# plugstrip.net
KiCad netlist of a schematic drawn in EAGLE
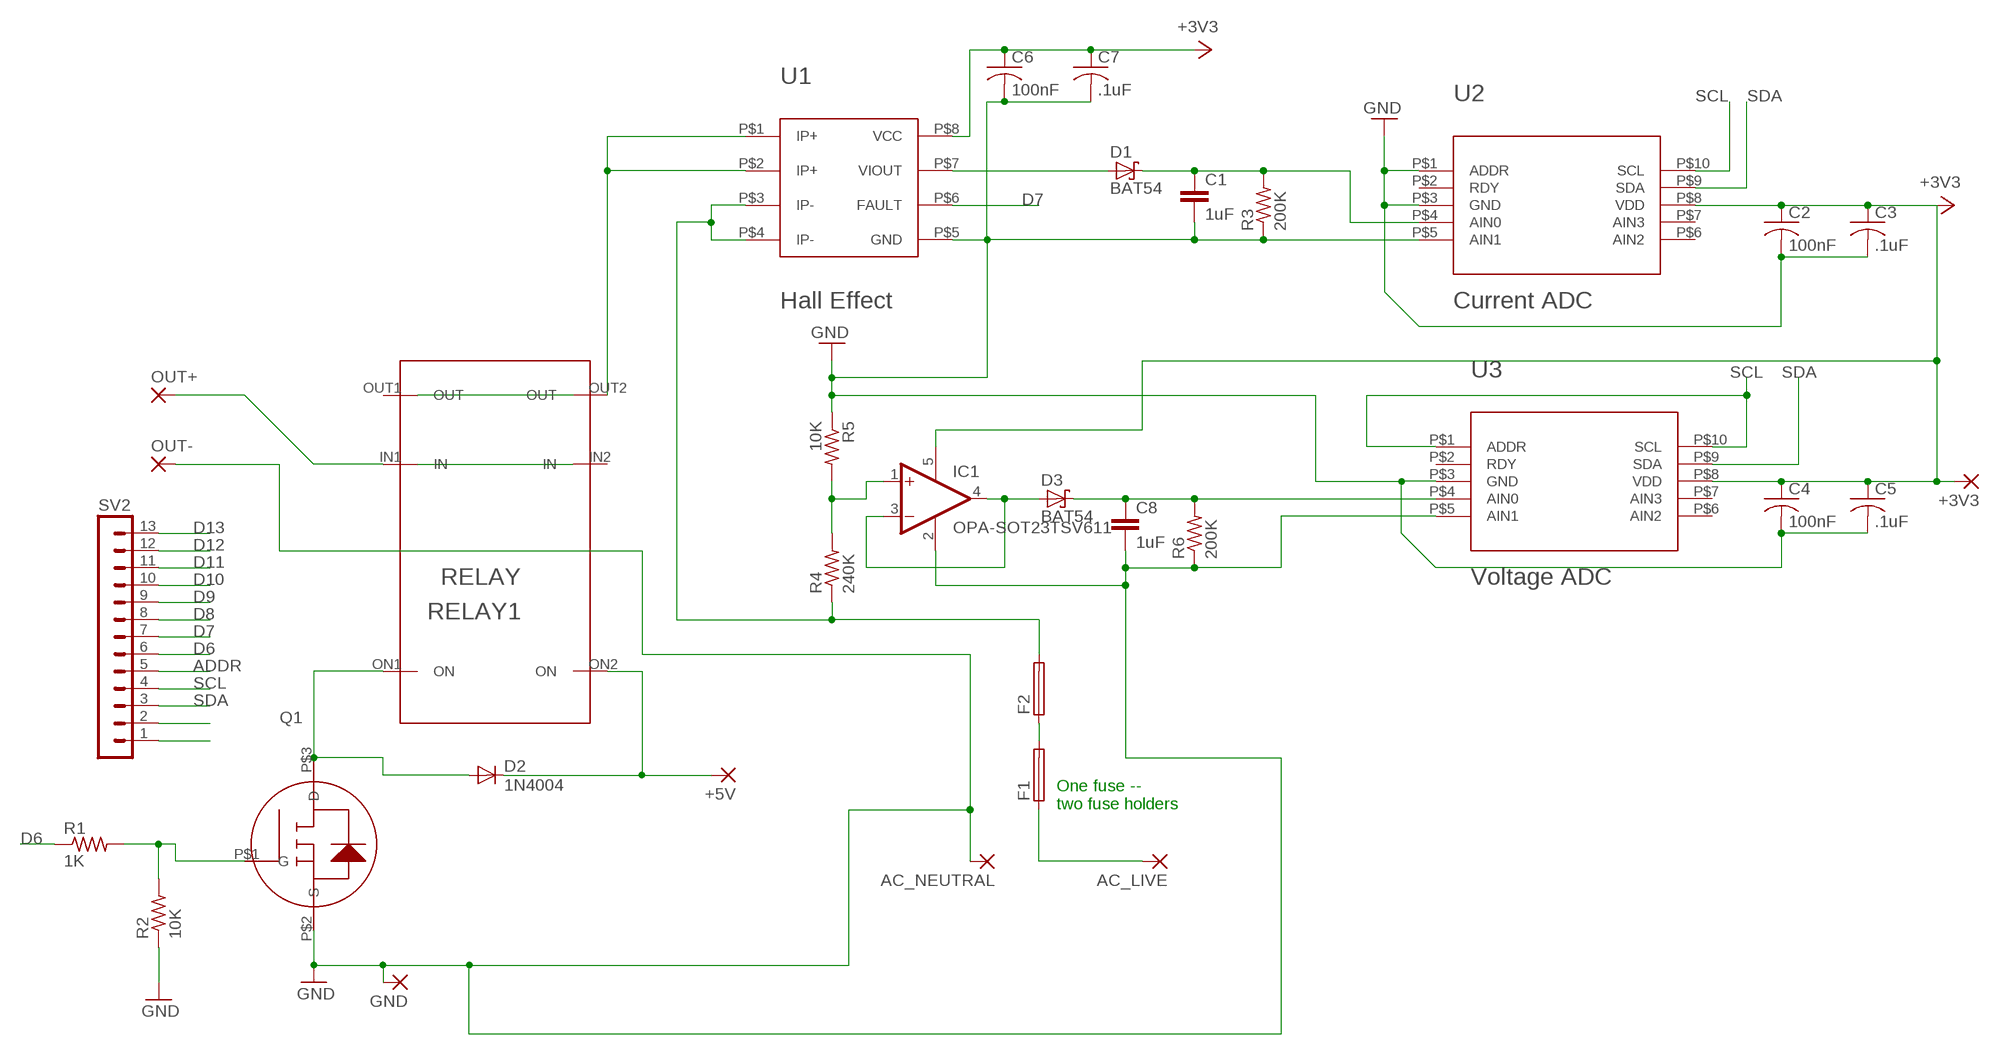
[diagram p0: schematic, sheet 1]

(export (version "E")
  (design (tool "Eeschema 10.0.6"))
  (components
    (comp (ref "+3V3")
      (value "3,81/1,4")
      (footprint "eagle-import:3,81_1,4")
      (libsource (lib "eagle-import") (part "3,81/1,4"))
    )
    (comp (ref "+5V")
      (value "3,81/1,4")
      (footprint "eagle-import:3,81_1,4")
      (libsource (lib "eagle-import") (part "3,81/1,4"))
    )
    (comp (ref "AC_LIVE")
      (value "3,81/1,4")
      (footprint "eagle-import:3,81_1,4")
      (libsource (lib "eagle-import") (part "3,81/1,4"))
    )
    (comp (ref "AC_NEUTRAL")
      (value "3,81/1,4")
      (footprint "eagle-import:3,81_1,4")
      (libsource (lib "eagle-import") (part "3,81/1,4"))
    )
    (comp (ref "C1")
      (value "1uF")
      (footprint "eagle-import:C2.5-2")
      (libsource (lib "eagle-import") (part "CSR215E105"))
    )
    (comp (ref "C2")
      (value "100nF")
      (footprint "eagle-import:C1206")
      (libsource (lib "eagle-import") (part "C-USC1206"))
    )
    (comp (ref "C3")
      (value ".1uF")
      (footprint "eagle-import:C1206")
      (libsource (lib "eagle-import") (part "C-USC1206"))
    )
    (comp (ref "C4")
      (value "100nF")
      (footprint "eagle-import:C1206")
      (libsource (lib "eagle-import") (part "C-USC1206"))
    )
    (comp (ref "C5")
      (value ".1uF")
      (footprint "eagle-import:C1206")
      (libsource (lib "eagle-import") (part "C-USC1206"))
    )
    (comp (ref "C6")
      (value "100nF")
      (footprint "eagle-import:C1206")
      (libsource (lib "eagle-import") (part "C-USC1206"))
    )
    (comp (ref "C7")
      (value ".1uF")
      (footprint "eagle-import:C1206")
      (libsource (lib "eagle-import") (part "C-USC1206"))
    )
    (comp (ref "C8")
      (value "1uF")
      (footprint "eagle-import:C2.5-2")
      (libsource (lib "eagle-import") (part "CSR215E105"))
    )
    (comp (ref "D1")
      (value "BAT54")
      (footprint "eagle-import:SOT23")
      (libsource (lib "eagle-import") (part "BAT54"))
    )
    (comp (ref "D2")
      (value "1N4004")
      (footprint "eagle-import:DO41-10")
      (libsource (lib "eagle-import") (part "1N4004"))
    )
    (comp (ref "D3")
      (value "BAT54")
      (footprint "eagle-import:SOT23")
      (libsource (lib "eagle-import") (part "BAT54"))
    )
    (comp (ref "F1")
      (value "19560")
      (footprint "eagle-import:19560")
      (fields (field (name "MPN") "56000001009"))
      (libsource (lib "eagle-import") (part "19560"))
    )
    (comp (ref "F2")
      (value "19560")
      (footprint "eagle-import:19560")
      (fields (field (name "MPN") "56000001009"))
      (libsource (lib "eagle-import") (part "19560"))
    )
    (comp (ref "GND")
      (value "3,81/1,4")
      (footprint "eagle-import:3,81_1,4")
      (libsource (lib "eagle-import") (part "3,81/1,4"))
    )
    (comp (ref "IC1")
      (value "OPA-SOT23TSV611")
      (footprint "eagle-import:SOT23-5")
      (libsource (lib "eagle-import") (part "OPA-SOT23TSV611"))
    )
    (comp (ref "OUT+")
      (value "3,81/1,4")
      (footprint "eagle-import:3,81_1,4")
      (libsource (lib "eagle-import") (part "3,81/1,4"))
    )
    (comp (ref "OUT-")
      (value "3,81/1,4")
      (footprint "eagle-import:3,81_1,4")
      (libsource (lib "eagle-import") (part "3,81/1,4"))
    )
    (comp (ref "Q1")
      (value "BSH105")
      (footprint "eagle-import:SOT23")
      (libsource (lib "eagle-import") (part "BSH105"))
    )
    (comp (ref "R1")
      (value "1K")
      (footprint "eagle-import:0411_15")
      (libsource (lib "eagle-import") (part "R-US_CT14J"))
    )
    (comp (ref "R2")
      (value "10K")
      (footprint "eagle-import:0411_15")
      (libsource (lib "eagle-import") (part "R-US_CT14J"))
    )
    (comp (ref "R3")
      (value "200K")
      (footprint "eagle-import:0411_15")
      (libsource (lib "eagle-import") (part "R-US_CT14J"))
    )
    (comp (ref "R4")
      (value "240K")
      (footprint "eagle-import:0411_15")
      (libsource (lib "eagle-import") (part "R-US_0411/15"))
    )
    (comp (ref "R5")
      (value "10K")
      (footprint "eagle-import:0411_15")
      (libsource (lib "eagle-import") (part "R-US_0411/15"))
    )
    (comp (ref "R6")
      (value "200K")
      (footprint "eagle-import:0411_15")
      (libsource (lib "eagle-import") (part "R-US_CT14J"))
    )
    (comp (ref "RELAY1")
      (value "RELAY")
      (footprint "eagle-import:G5RL-1A-E-HR")
      (libsource (lib "eagle-import") (part "G5RL-1A-E-HR"))
    )
    (comp (ref "SV2")
      (value "MA13-1")
      (footprint "eagle-import:MA13-1")
      (libsource (lib "eagle-import") (part "MA13-1"))
    )
    (comp (ref "U1")
      (value "Hall Effect")
      (footprint "eagle-import:ACS711")
      (libsource (lib "eagle-import") (part "ACS711LC"))
    )
    (comp (ref "U2")
      (value "Current ADC")
      (footprint "eagle-import:ADS1013")
      (libsource (lib "eagle-import") (part "ADS1013IDGST"))
    )
    (comp (ref "U3")
      (value "Voltage ADC")
      (footprint "eagle-import:ADS1013")
      (libsource (lib "eagle-import") (part "ADS1013IDGST"))
    )
  )
  (nets
    (net (code "1") (name "+3V3") (class "Default")
      (node (ref "+3V3") (pin "1") (pinfunction "P_1") (pintype "passive"))
      (node (ref "C2") (pin "1") (pinfunction "1_1") (pintype "passive"))
      (node (ref "C3") (pin "1") (pinfunction "1_1") (pintype "passive"))
      (node (ref "C4") (pin "1") (pinfunction "1_1") (pintype "passive"))
      (node (ref "C5") (pin "1") (pinfunction "1_1") (pintype "passive"))
      (node (ref "C6") (pin "1") (pinfunction "1_1") (pintype "passive"))
      (node (ref "C7") (pin "1") (pinfunction "1_1") (pintype "passive"))
      (node (ref "IC1") (pin "5") (pinfunction "V+_5") (pintype "power_in"))
      (node (ref "U1") (pin "P$8") (pinfunction "VCC_P$8") (pintype "power_in"))
      (node (ref "U2") (pin "P$8") (pinfunction "VDD_P$8") (pintype "power_in"))
      (node (ref "U3") (pin "P$8") (pinfunction "VDD_P$8") (pintype "power_in"))
    )
    (net (code "2") (name "/ADDR") (class "Default")
      (node (ref "SV2") (pin "5") (pinfunction "5_5") (pintype "passive"))
    )
    (net (code "3") (name "/D6") (class "Default")
      (node (ref "R1") (pin "1") (pinfunction "1_1") (pintype "passive"))
      (node (ref "SV2") (pin "6") (pinfunction "6_6") (pintype "passive"))
    )
    (net (code "4") (name "/D7") (class "Default")
      (node (ref "SV2") (pin "7") (pinfunction "7_7") (pintype "passive"))
      (node (ref "U1") (pin "P$6") (pinfunction "FAULT_P$6") (pintype "bidirectional"))
    )
    (net (code "5") (name "/D8") (class "Default")
      (node (ref "SV2") (pin "8") (pinfunction "8_8") (pintype "passive"))
    )
    (net (code "6") (name "/D9") (class "Default")
      (node (ref "SV2") (pin "9") (pinfunction "9_9") (pintype "passive"))
    )
    (net (code "7") (name "/D10") (class "Default")
      (node (ref "SV2") (pin "10") (pinfunction "10_10") (pintype "passive"))
    )
    (net (code "8") (name "/D11") (class "Default")
      (node (ref "SV2") (pin "11") (pinfunction "11_11") (pintype "passive"))
    )
    (net (code "9") (name "/D12") (class "Default")
      (node (ref "SV2") (pin "12") (pinfunction "12_12") (pintype "passive"))
    )
    (net (code "10") (name "/D13") (class "Default")
      (node (ref "SV2") (pin "13") (pinfunction "13_13") (pintype "passive"))
    )
    (net (code "11") (name "/SCL") (class "Default")
      (node (ref "SV2") (pin "4") (pinfunction "4_4") (pintype "passive"))
      (node (ref "U2") (pin "P$10") (pinfunction "SCL_P$10") (pintype "bidirectional"))
      (node (ref "U3") (pin "P$1") (pinfunction "ADDR_P$1") (pintype "bidirectional"))
      (node (ref "U3") (pin "P$10") (pinfunction "SCL_P$10") (pintype "bidirectional"))
    )
    (net (code "12") (name "/SDA") (class "Default")
      (node (ref "SV2") (pin "3") (pinfunction "3_3") (pintype "passive"))
      (node (ref "U2") (pin "P$9") (pinfunction "SDA_P$9") (pintype "bidirectional"))
      (node (ref "U3") (pin "P$9") (pinfunction "SDA_P$9") (pintype "bidirectional"))
    )
    (net (code "13") (name "GND") (class "Default")
      (node (ref "AC_NEUTRAL") (pin "1") (pinfunction "P_1") (pintype "passive"))
      (node (ref "C1") (pin "2") (pinfunction "2_2") (pintype "passive"))
      (node (ref "C2") (pin "2") (pinfunction "2_2") (pintype "passive"))
      (node (ref "C3") (pin "2") (pinfunction "2_2") (pintype "passive"))
      (node (ref "C4") (pin "2") (pinfunction "2_2") (pintype "passive"))
      (node (ref "C5") (pin "2") (pinfunction "2_2") (pintype "passive"))
      (node (ref "C6") (pin "2") (pinfunction "2_2") (pintype "passive"))
      (node (ref "C7") (pin "2") (pinfunction "2_2") (pintype "passive"))
      (node (ref "C8") (pin "2") (pinfunction "2_2") (pintype "passive"))
      (node (ref "GND") (pin "1") (pinfunction "P_1") (pintype "passive"))
      (node (ref "IC1") (pin "2") (pinfunction "V-_2") (pintype "power_in"))
      (node (ref "OUT-") (pin "1") (pinfunction "P_1") (pintype "passive"))
      (node (ref "Q1") (pin "P$2") (pinfunction "S_P$2") (pintype "input"))
      (node (ref "R2") (pin "1") (pinfunction "1_1") (pintype "passive"))
      (node (ref "R3") (pin "1") (pinfunction "1_1") (pintype "passive"))
      (node (ref "R5") (pin "1") (pinfunction "1_1") (pintype "passive"))
      (node (ref "R6") (pin "1") (pinfunction "1_1") (pintype "passive"))
      (node (ref "U1") (pin "P$5") (pinfunction "GND_P$5") (pintype "power_in"))
      (node (ref "U2") (pin "P$1") (pinfunction "ADDR_P$1") (pintype "bidirectional"))
      (node (ref "U2") (pin "P$3") (pinfunction "GND_P$3") (pintype "power_in"))
      (node (ref "U2") (pin "P$5") (pinfunction "AIN1_P$5") (pintype "bidirectional"))
      (node (ref "U3") (pin "P$3") (pinfunction "GND_P$3") (pintype "power_in"))
      (node (ref "U3") (pin "P$5") (pinfunction "AIN1_P$5") (pintype "bidirectional"))
    )
    (net (code "14") (name "Net-(+5V-P)") (class "Default")
      (node (ref "+5V") (pin "1") (pinfunction "P_1") (pintype "passive"))
      (node (ref "D2") (pin "C") (pinfunction "C_C") (pintype "passive"))
      (node (ref "RELAY1") (pin "ON2") (pinfunction "ON_ON2") (pintype "bidirectional"))
    )
    (net (code "15") (name "Net-(AC_LIVE-P)") (class "Default")
      (node (ref "AC_LIVE") (pin "1") (pinfunction "P_1") (pintype "passive"))
      (node (ref "F1") (pin "1") (pinfunction "1_1") (pintype "passive"))
    )
    (net (code "16") (name "Net-(D1-A)") (class "Default")
      (node (ref "D1") (pin "1") (pinfunction "A_1") (pintype "passive"))
      (node (ref "U1") (pin "P$7") (pinfunction "VIOUT_P$7") (pintype "bidirectional"))
    )
    (net (code "17") (name "Net-(D1-C)") (class "Default")
      (node (ref "C1") (pin "1") (pinfunction "1_1") (pintype "passive"))
      (node (ref "D1") (pin "3") (pinfunction "C_3") (pintype "passive"))
      (node (ref "R3") (pin "2") (pinfunction "2_2") (pintype "passive"))
      (node (ref "U2") (pin "P$4") (pinfunction "AIN0_P$4") (pintype "bidirectional"))
    )
    (net (code "18") (name "Net-(D3-A)") (class "Default")
      (node (ref "D3") (pin "1") (pinfunction "A_1") (pintype "passive"))
      (node (ref "IC1") (pin "3") (pinfunction "-IN_3") (pintype "input"))
      (node (ref "IC1") (pin "4") (pinfunction "OUT_4") (pintype "output"))
    )
    (net (code "19") (name "Net-(D3-C)") (class "Default")
      (node (ref "C8") (pin "1") (pinfunction "1_1") (pintype "passive"))
      (node (ref "D3") (pin "3") (pinfunction "C_3") (pintype "passive"))
      (node (ref "R6") (pin "2") (pinfunction "2_2") (pintype "passive"))
      (node (ref "U3") (pin "P$4") (pinfunction "AIN0_P$4") (pintype "bidirectional"))
    )
    (net (code "20") (name "Net-(F1-Pad2)") (class "Default")
      (node (ref "F1") (pin "2") (pinfunction "2_2") (pintype "passive"))
      (node (ref "F2") (pin "1") (pinfunction "1_1") (pintype "passive"))
    )
    (net (code "21") (name "Net-(F2-Pad2)") (class "Default")
      (node (ref "F2") (pin "2") (pinfunction "2_2") (pintype "passive"))
      (node (ref "R4") (pin "1") (pinfunction "1_1") (pintype "passive"))
      (node (ref "U1") (pin "P$3") (pinfunction "IP-_P$3") (pintype "bidirectional"))
      (node (ref "U1") (pin "P$4") (pinfunction "IP-_P$4") (pintype "bidirectional"))
    )
    (net (code "22") (name "Net-(IC1-+IN)") (class "Default")
      (node (ref "IC1") (pin "1") (pinfunction "+IN_1") (pintype "input"))
      (node (ref "R4") (pin "2") (pinfunction "2_2") (pintype "passive"))
      (node (ref "R5") (pin "2") (pinfunction "2_2") (pintype "passive"))
    )
    (net (code "23") (name "Net-(OUT+-P)") (class "Default")
      (node (ref "OUT+") (pin "1") (pinfunction "P_1") (pintype "passive"))
      (node (ref "RELAY1") (pin "IN1") (pinfunction "IN_IN1") (pintype "bidirectional"))
    )
    (net (code "24") (name "Net-(Q1-D)") (class "Default")
      (node (ref "D2") (pin "A") (pinfunction "A_A") (pintype "passive"))
      (node (ref "Q1") (pin "P$3") (pinfunction "D_P$3") (pintype "input"))
      (node (ref "RELAY1") (pin "ON1") (pinfunction "ON_ON1") (pintype "bidirectional"))
    )
    (net (code "25") (name "Net-(Q1-G)") (class "Default")
      (node (ref "Q1") (pin "P$1") (pinfunction "G_P$1") (pintype "output"))
      (node (ref "R1") (pin "2") (pinfunction "2_2") (pintype "passive"))
      (node (ref "R2") (pin "2") (pinfunction "2_2") (pintype "passive"))
    )
    (net (code "26") (name "Net-(RELAY1-OUT-PadOUT2)") (class "Default")
      (node (ref "RELAY1") (pin "OUT2") (pinfunction "OUT_OUT2") (pintype "bidirectional"))
      (node (ref "U1") (pin "P$1") (pinfunction "IP+_P$1") (pintype "bidirectional"))
      (node (ref "U1") (pin "P$2") (pinfunction "IP+_P$2") (pintype "bidirectional"))
    )
    (net (code "27") (name "unconnected-(RELAY1-IN-PadIN2)") (class "Default")
      (node (ref "RELAY1") (pin "IN2") (pinfunction "IN_IN2") (pintype "bidirectional"))
    )
    (net (code "28") (name "unconnected-(RELAY1-OUT-PadOUT1)") (class "Default")
      (node (ref "RELAY1") (pin "OUT1") (pinfunction "OUT_OUT1") (pintype "bidirectional"))
    )
    (net (code "29") (name "unconnected-(SV2-Pad1)") (class "Default")
      (node (ref "SV2") (pin "1") (pinfunction "1_1") (pintype "passive"))
    )
    (net (code "30") (name "unconnected-(SV2-Pad2)") (class "Default")
      (node (ref "SV2") (pin "2") (pinfunction "2_2") (pintype "passive"))
    )
    (net (code "31") (name "unconnected-(U2-AIN2-PadP$6)") (class "Default")
      (node (ref "U2") (pin "P$6") (pinfunction "AIN2_P$6") (pintype "no_connect"))
    )
    (net (code "32") (name "unconnected-(U2-AIN3-PadP$7)") (class "Default")
      (node (ref "U2") (pin "P$7") (pinfunction "AIN3_P$7") (pintype "no_connect"))
    )
    (net (code "33") (name "unconnected-(U2-RDY-PadP$2)") (class "Default")
      (node (ref "U2") (pin "P$2") (pinfunction "RDY_P$2") (pintype "no_connect"))
    )
    (net (code "34") (name "unconnected-(U3-AIN2-PadP$6)") (class "Default")
      (node (ref "U3") (pin "P$6") (pinfunction "AIN2_P$6") (pintype "no_connect"))
    )
    (net (code "35") (name "unconnected-(U3-AIN3-PadP$7)") (class "Default")
      (node (ref "U3") (pin "P$7") (pinfunction "AIN3_P$7") (pintype "no_connect"))
    )
    (net (code "36") (name "unconnected-(U3-RDY-PadP$2)") (class "Default")
      (node (ref "U3") (pin "P$2") (pinfunction "RDY_P$2") (pintype "no_connect"))
    )
  )
)
